# Video_critter_v01.net
KiCad netlist of a schematic drawn in EAGLE
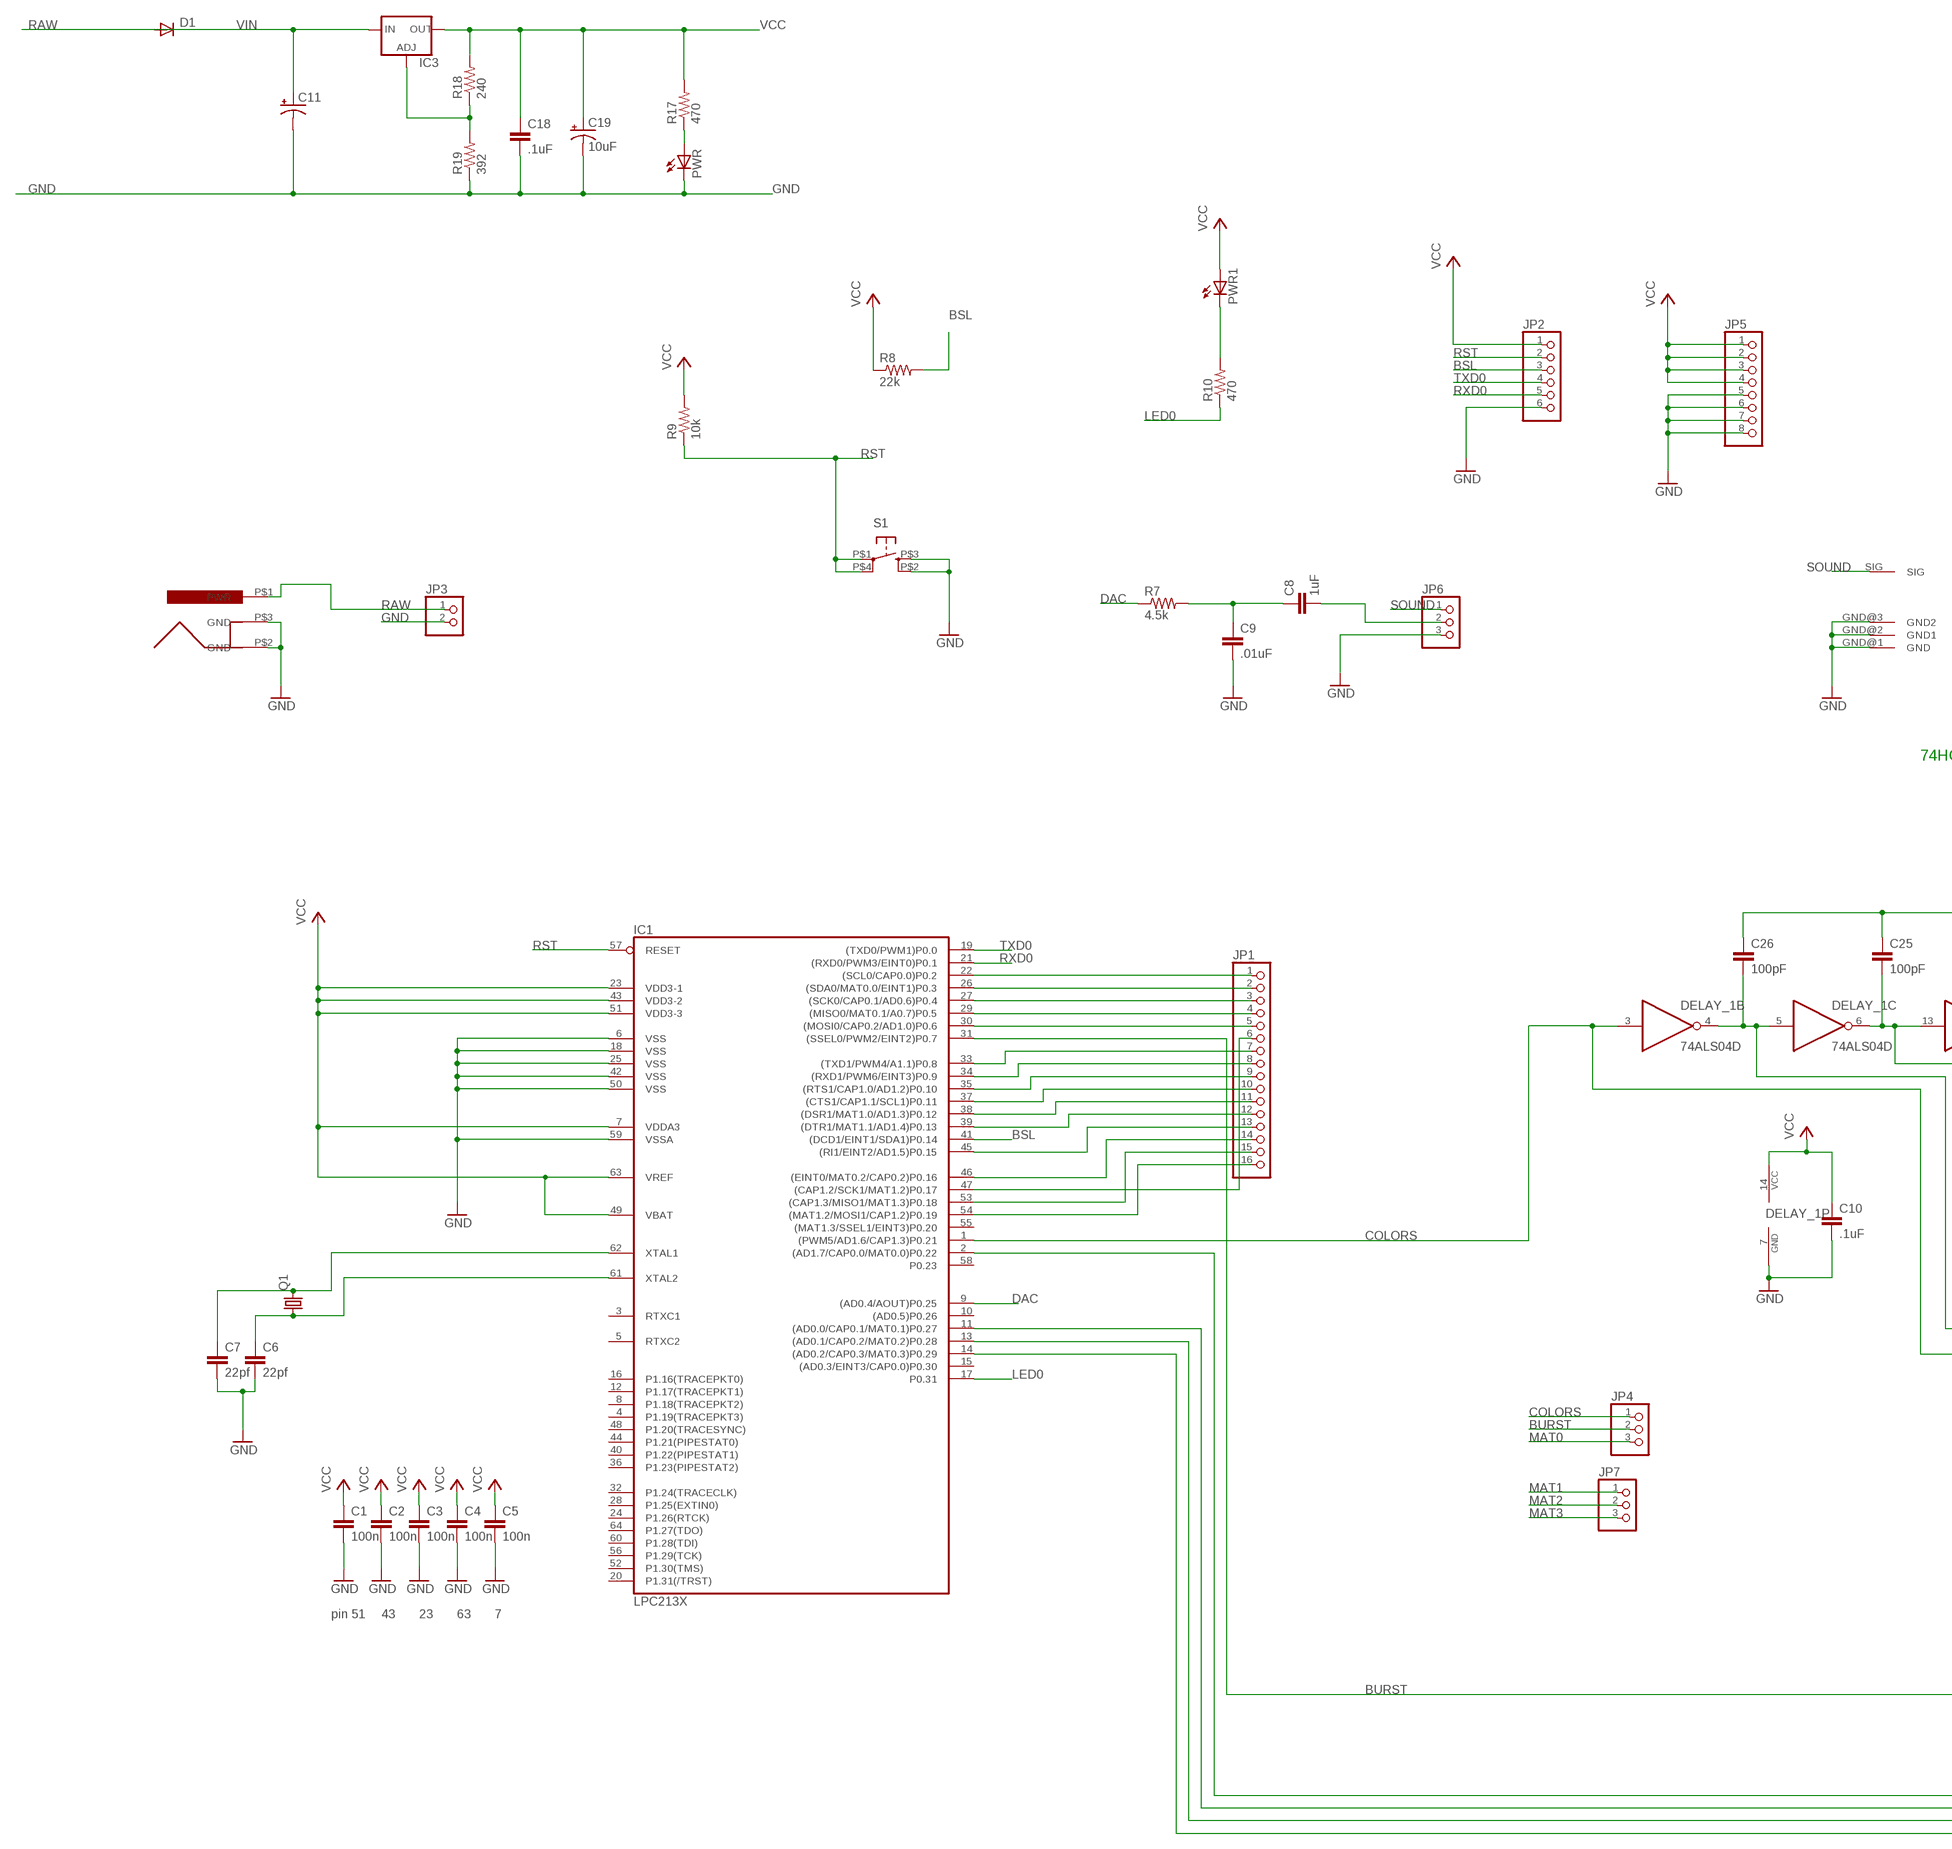
[diagram p0: schematic, sheet 1, part 1 of 2]
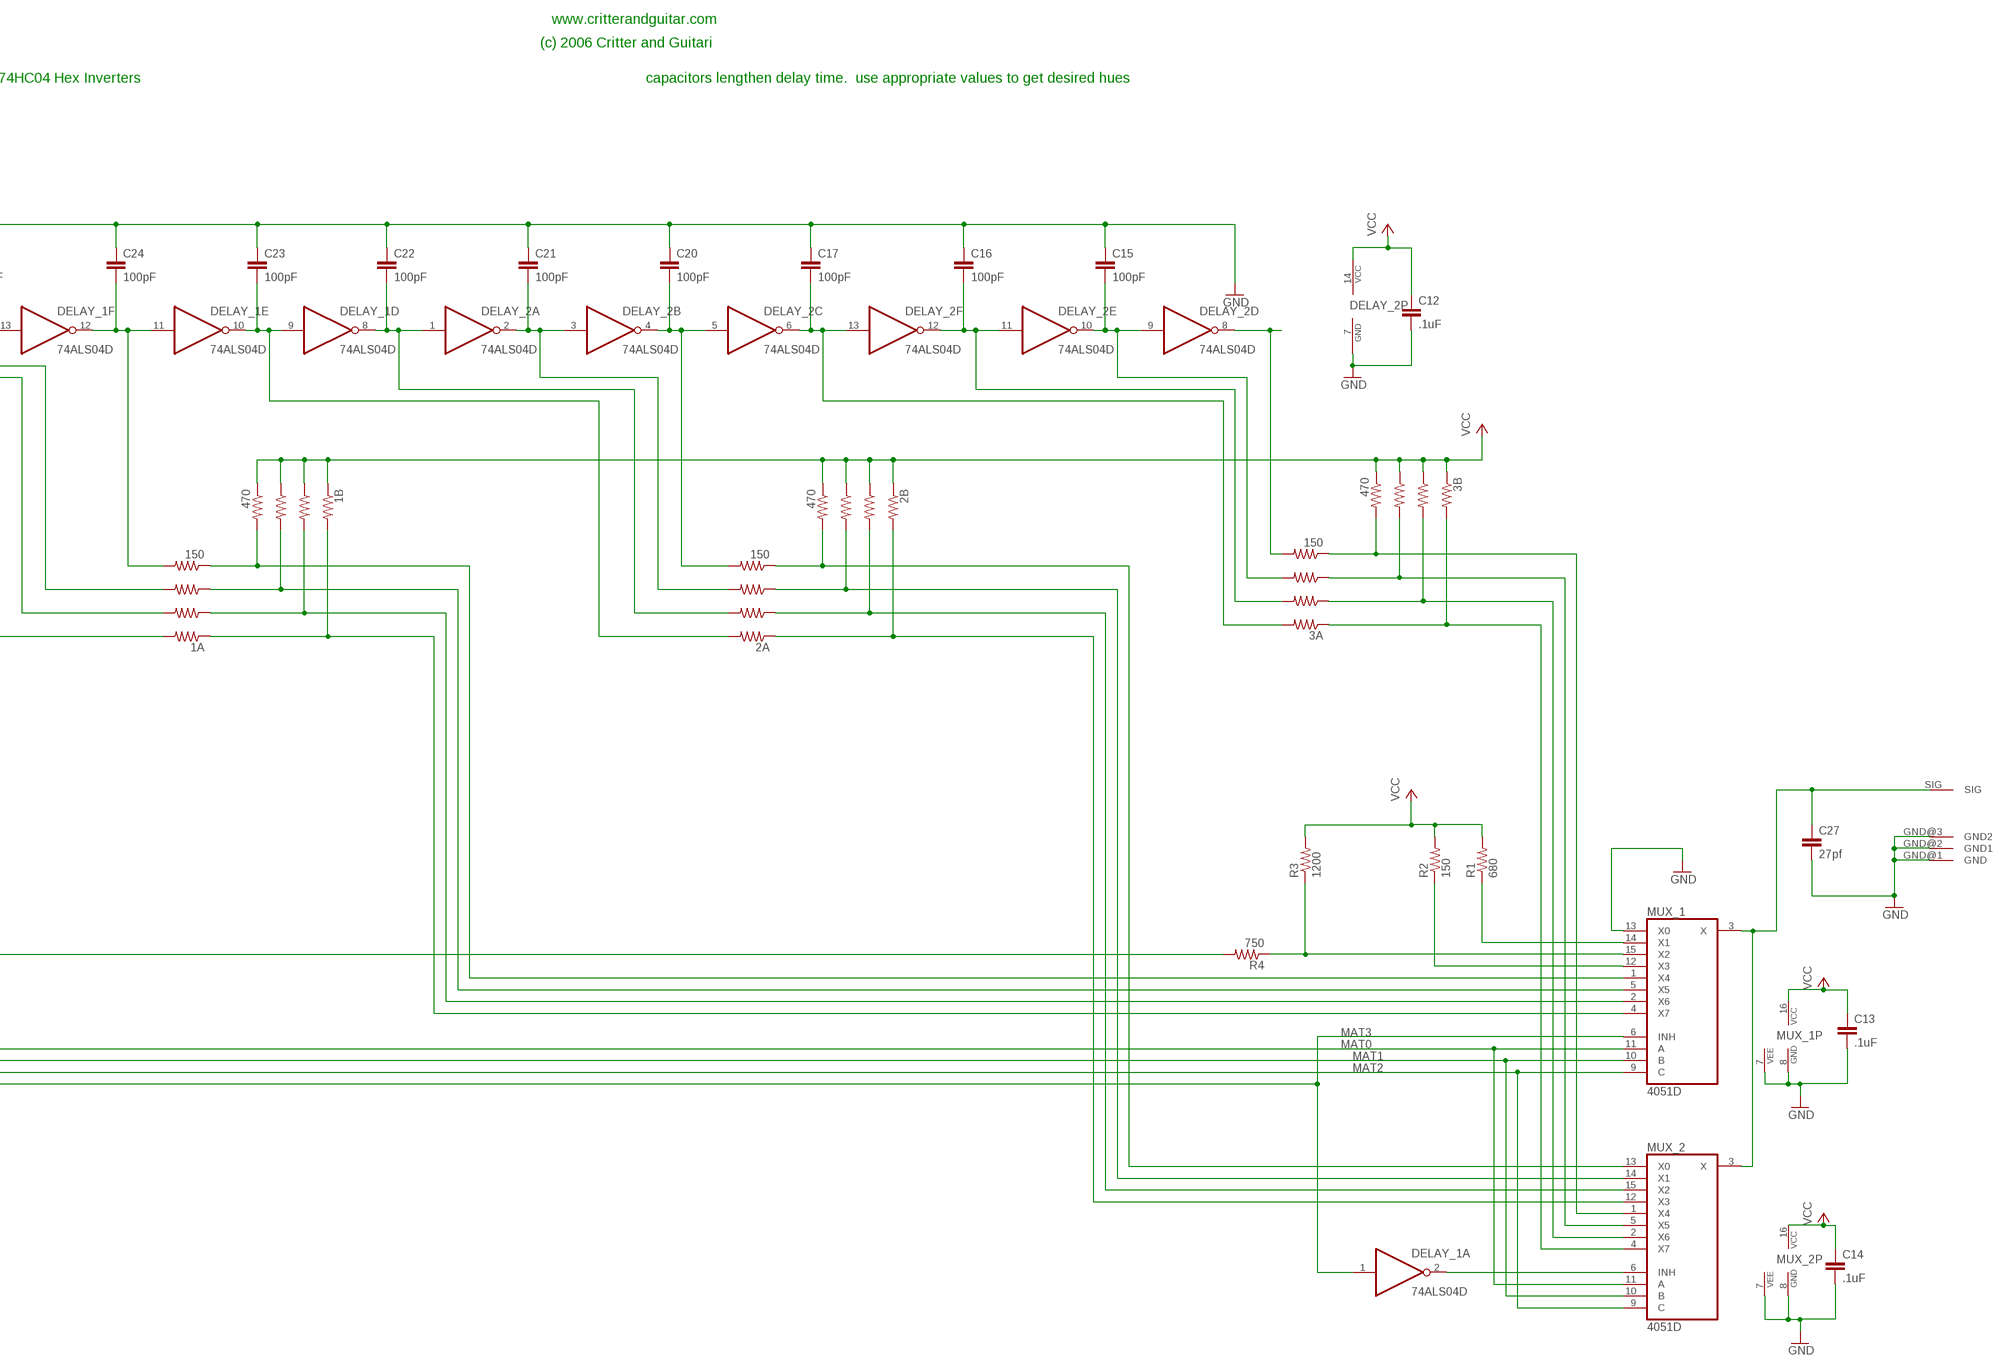
[diagram p1: schematic, sheet 1, part 2 of 2]

(export (version "E")
  (design (tool "Eeschema 10.0.6"))
  (components
    (comp (ref "1A")
      (value "150")
      (footprint "eagle-import:1206X4RESISTOR")
      (libsource (lib "eagle-import") (part "RESISTORX41206"))
    )
    (comp (ref "1B")
      (value "470")
      (footprint "eagle-import:1206X4RESISTOR")
      (libsource (lib "eagle-import") (part "RESISTORX41206"))
    )
    (comp (ref "2A")
      (value "150")
      (footprint "eagle-import:1206X4RESISTOR")
      (libsource (lib "eagle-import") (part "RESISTORX41206"))
    )
    (comp (ref "2B")
      (value "470")
      (footprint "eagle-import:1206X4RESISTOR")
      (libsource (lib "eagle-import") (part "RESISTORX41206"))
    )
    (comp (ref "3A")
      (value "150")
      (footprint "eagle-import:1206X4RESISTOR")
      (libsource (lib "eagle-import") (part "RESISTORX41206"))
    )
    (comp (ref "3B")
      (value "470")
      (footprint "eagle-import:1206X4RESISTOR")
      (libsource (lib "eagle-import") (part "RESISTORX41206"))
    )
    (comp (ref "C1")
      (value "100n")
      (footprint "eagle-import:C0603")
      (libsource (lib "eagle-import") (part "CAP0603"))
    )
    (comp (ref "C2")
      (value "100n")
      (footprint "eagle-import:C0603")
      (libsource (lib "eagle-import") (part "CAP0603"))
    )
    (comp (ref "C3")
      (value "100n")
      (footprint "eagle-import:C0603")
      (libsource (lib "eagle-import") (part "CAP0603"))
    )
    (comp (ref "C4")
      (value "100n")
      (footprint "eagle-import:C0603")
      (libsource (lib "eagle-import") (part "CAP0603"))
    )
    (comp (ref "C5")
      (value "100n")
      (footprint "eagle-import:C0603")
      (libsource (lib "eagle-import") (part "CAP0603"))
    )
    (comp (ref "C6")
      (value "22pf")
      (footprint "eagle-import:C0603")
      (libsource (lib "eagle-import") (part "CAP0603"))
    )
    (comp (ref "C7")
      (value "22pf")
      (footprint "eagle-import:C0603")
      (libsource (lib "eagle-import") (part "CAP0603"))
    )
    (comp (ref "C8")
      (value "1uF")
      (footprint "eagle-import:C0603")
      (libsource (lib "eagle-import") (part "CAP0603"))
    )
    (comp (ref "C9")
      (value ".01uF")
      (footprint "eagle-import:C0603")
      (libsource (lib "eagle-import") (part "CAP0603"))
    )
    (comp (ref "C10")
      (value ".1uF")
      (footprint "eagle-import:C0603")
      (libsource (lib "eagle-import") (part "CAP0603"))
    )
    (comp (ref "C11")
      (value "CPOL-USE3.5-8")
      (footprint "eagle-import:E3,5-8")
      (libsource (lib "eagle-import") (part "CPOL-USE3.5-8"))
    )
    (comp (ref "C12")
      (value ".1uF")
      (footprint "eagle-import:C0603")
      (libsource (lib "eagle-import") (part "CAP0603"))
    )
    (comp (ref "C13")
      (value ".1uF")
      (footprint "eagle-import:C0603")
      (libsource (lib "eagle-import") (part "CAP0603"))
    )
    (comp (ref "C14")
      (value ".1uF")
      (footprint "eagle-import:C0603")
      (libsource (lib "eagle-import") (part "CAP0603"))
    )
    (comp (ref "C15")
      (value "100pF")
      (footprint "eagle-import:C0603")
      (libsource (lib "eagle-import") (part "CAP0603"))
    )
    (comp (ref "C16")
      (value "100pF")
      (footprint "eagle-import:C0603")
      (libsource (lib "eagle-import") (part "CAP0603"))
    )
    (comp (ref "C17")
      (value "100pF")
      (footprint "eagle-import:C0603")
      (libsource (lib "eagle-import") (part "CAP0603"))
    )
    (comp (ref "C18")
      (value ".1uF")
      (footprint "eagle-import:C0603")
      (libsource (lib "eagle-import") (part "CAP0603"))
    )
    (comp (ref "C19")
      (value "10uF")
      (footprint "eagle-import:CPOL_1206")
      (libsource (lib "eagle-import") (part "CAP_POL1206"))
    )
    (comp (ref "C20")
      (value "100pF")
      (footprint "eagle-import:C0603")
      (libsource (lib "eagle-import") (part "CAP0603"))
    )
    (comp (ref "C21")
      (value "100pF")
      (footprint "eagle-import:C0603")
      (libsource (lib "eagle-import") (part "CAP0603"))
    )
    (comp (ref "C22")
      (value "100pF")
      (footprint "eagle-import:C0603")
      (libsource (lib "eagle-import") (part "CAP0603"))
    )
    (comp (ref "C23")
      (value "100pF")
      (footprint "eagle-import:C0603")
      (libsource (lib "eagle-import") (part "CAP0603"))
    )
    (comp (ref "C24")
      (value "100pF")
      (footprint "eagle-import:C0603")
      (libsource (lib "eagle-import") (part "CAP0603"))
    )
    (comp (ref "C25")
      (value "100pF")
      (footprint "eagle-import:C0603")
      (libsource (lib "eagle-import") (part "CAP0603"))
    )
    (comp (ref "C26")
      (value "100pF")
      (footprint "eagle-import:C0603")
      (libsource (lib "eagle-import") (part "CAP0603"))
    )
    (comp (ref "C27")
      (value "27pf")
      (footprint "eagle-import:C0603")
      (libsource (lib "eagle-import") (part "CAP0603"))
    )
    (comp (ref "D1")
      (value "DIODESMB")
      (footprint "eagle-import:SMB")
      (libsource (lib "eagle-import") (part "DIODESMB"))
    )
    (comp (ref "DELAY_1")
      (value "74ALS04D")
      (footprint "eagle-import:SO14")
      (libsource (lib "eagle-import") (part "7404DALS"))
    )
    (comp (ref "DELAY_2")
      (value "74ALS04D")
      (footprint "eagle-import:SO14")
      (libsource (lib "eagle-import") (part "7404DALS"))
    )
    (comp (ref "IC1")
      (value "LPC213X")
      (footprint "eagle-import:SQFP-S-10X10-64")
      (libsource (lib "eagle-import") (part "LPC213X"))
    )
    (comp (ref "IC3")
      (value "V_REG_FAN1117SOT223")
      (footprint "eagle-import:SOT223")
      (libsource (lib "eagle-import") (part "V_REG_FAN1117SOT223"))
    )
    (comp (ref "JP1")
      (value "PINHD-1X16")
      (footprint "eagle-import:1X16")
      (libsource (lib "eagle-import") (part "PINHD-1X16"))
    )
    (comp (ref "JP2")
      (value "PINHD-1X6")
      (footprint "eagle-import:1X06")
      (libsource (lib "eagle-import") (part "PINHD-1X6"))
    )
    (comp (ref "JP3")
      (value "PINHD-1X2")
      (footprint "eagle-import:1X02")
      (libsource (lib "eagle-import") (part "PINHD-1X2"))
    )
    (comp (ref "JP4")
      (value "PINHD-1X3")
      (footprint "eagle-import:1X03")
      (libsource (lib "eagle-import") (part "PINHD-1X3"))
    )
    (comp (ref "JP5")
      (value "PINHD-1X8")
      (footprint "eagle-import:1X08")
      (libsource (lib "eagle-import") (part "PINHD-1X8"))
    )
    (comp (ref "JP6")
      (value "PINHD-1X3")
      (footprint "eagle-import:1X03")
      (libsource (lib "eagle-import") (part "PINHD-1X3"))
    )
    (comp (ref "JP7")
      (value "PINHD-1X3")
      (footprint "eagle-import:1X03")
      (libsource (lib "eagle-import") (part "PINHD-1X3"))
    )
    (comp (ref "MUX_1")
      (value "4051D")
      (footprint "eagle-import:SO16")
      (libsource (lib "eagle-import") (part "4051D"))
    )
    (comp (ref "MUX_2")
      (value "4051D")
      (footprint "eagle-import:SO16")
      (libsource (lib "eagle-import") (part "4051D"))
    )
    (comp (ref "PWR")
      (value "LED1206")
      (footprint "eagle-import:CHIPLED_1206")
      (libsource (lib "eagle-import") (part "LED1206"))
    )
    (comp (ref "PWR1")
      (value "LED1206")
      (footprint "eagle-import:CHIPLED_1206")
      (libsource (lib "eagle-import") (part "LED1206"))
    )
    (comp (ref "Q1")
      (value "CRYSTALSOCKETED")
      (footprint "eagle-import:HC49U-SOCKETED")
      (libsource (lib "eagle-import") (part "CRYSTALSOCKETED"))
    )
    (comp (ref "R1")
      (value "680")
      (footprint "eagle-import:R0603")
      (libsource (lib "eagle-import") (part "RES0603"))
    )
    (comp (ref "R2")
      (value "150")
      (footprint "eagle-import:R0603")
      (libsource (lib "eagle-import") (part "RES0603"))
    )
    (comp (ref "R3")
      (value "1200")
      (footprint "eagle-import:R0603")
      (libsource (lib "eagle-import") (part "RES0603"))
    )
    (comp (ref "R4")
      (value "750")
      (footprint "eagle-import:R0603")
      (libsource (lib "eagle-import") (part "RES0603"))
    )
    (comp (ref "R7")
      (value "4.5k")
      (footprint "eagle-import:R0603")
      (libsource (lib "eagle-import") (part "RES0603"))
    )
    (comp (ref "R8")
      (value "22k")
      (footprint "eagle-import:R0603")
      (libsource (lib "eagle-import") (part "RES0603"))
    )
    (comp (ref "R9")
      (value "10k")
      (footprint "eagle-import:R0603")
      (libsource (lib "eagle-import") (part "RES0603"))
    )
    (comp (ref "R10")
      (value "470")
      (footprint "eagle-import:R0603")
      (libsource (lib "eagle-import") (part "RES0603"))
    )
    (comp (ref "R17")
      (value "470")
      (footprint "eagle-import:R0603")
      (libsource (lib "eagle-import") (part "RES0603"))
    )
    (comp (ref "R18")
      (value "240")
      (footprint "eagle-import:R0603")
      (libsource (lib "eagle-import") (part "RES0603"))
    )
    (comp (ref "R19")
      (value "392")
      (footprint "eagle-import:R0603")
      (libsource (lib "eagle-import") (part "RES0603"))
    )
    (comp (ref "S1")
      (value "TAC_SWITCH")
      (footprint "eagle-import:TACTILE_SWITCH_SMD")
      (libsource (lib "eagle-import") (part "TAC_SWITCH"))
    )
    (comp (ref "U$1")
      (value "POWER_JACK")
      (footprint "eagle-import:POWER_JACK")
      (libsource (lib "eagle-import") (part "POWER_JACKTHRU-HOLE"))
    )
    (comp (ref "U$5")
      (value "PHONO_PLUG")
      (footprint "eagle-import:PHONO_PCB")
      (libsource (lib "eagle-import") (part "PHONO_PLUG"))
    )
    (comp (ref "U$6")
      (value "PHONO_PLUG")
      (footprint "eagle-import:PHONO_PCB")
      (libsource (lib "eagle-import") (part "PHONO_PLUG"))
    )
  )
  (nets
    (net (code "1") (name "/BSL") (class "Default")
      (node (ref "IC1") (pin "41") (pinfunction "(DCD1/EINT1/SDA1)P0.14_41") (pintype "bidirectional"))
      (node (ref "JP2") (pin "3") (pinfunction "3_3") (pintype "passive"))
      (node (ref "R8") (pin "2") (pinfunction "2_2") (pintype "passive"))
    )
    (net (code "2") (name "/BURST") (class "Default")
      (node (ref "IC1") (pin "31") (pinfunction "(SSEL0/PWM2/EINT2)P0.7_31") (pintype "bidirectional"))
      (node (ref "JP4") (pin "2") (pinfunction "2_2") (pintype "passive"))
      (node (ref "R4") (pin "2") (pinfunction "2_2") (pintype "passive"))
    )
    (net (code "3") (name "/COLORS") (class "Default")
      (node (ref "1A") (pin "P$8") (pinfunction "7_P$8") (pintype "passive"))
      (node (ref "DELAY_1") (pin "3") (pinfunction "I_3") (pintype "input"))
      (node (ref "IC1") (pin "1") (pinfunction "(PWM5/AD1.6/CAP1.3)P0.21_1") (pintype "bidirectional"))
      (node (ref "JP4") (pin "1") (pinfunction "1_1") (pintype "passive"))
    )
    (net (code "4") (name "/DAC") (class "Default")
      (node (ref "IC1") (pin "9") (pinfunction "(AD0.4/AOUT)P0.25_9") (pintype "bidirectional"))
      (node (ref "R7") (pin "1") (pinfunction "1_1") (pintype "passive"))
    )
    (net (code "5") (name "/LED0") (class "Default")
      (node (ref "IC1") (pin "17") (pinfunction "P0.31_17") (pintype "output"))
      (node (ref "R10") (pin "1") (pinfunction "1_1") (pintype "passive"))
    )
    (net (code "6") (name "/MAT0") (class "Default")
      (node (ref "IC1") (pin "2") (pinfunction "(AD1.7/CAP0.0/MAT0.0)P0.22_2") (pintype "bidirectional"))
      (node (ref "JP4") (pin "3") (pinfunction "3_3") (pintype "passive"))
      (node (ref "MUX_1") (pin "11") (pinfunction "A_11") (pintype "input"))
      (node (ref "MUX_2") (pin "11") (pinfunction "A_11") (pintype "input"))
    )
    (net (code "7") (name "/MAT1") (class "Default")
      (node (ref "IC1") (pin "11") (pinfunction "(AD0.0/CAP0.1/MAT0.1)P0.27_11") (pintype "bidirectional"))
      (node (ref "JP7") (pin "1") (pinfunction "1_1") (pintype "passive"))
      (node (ref "MUX_1") (pin "10") (pinfunction "B_10") (pintype "input"))
      (node (ref "MUX_2") (pin "10") (pinfunction "B_10") (pintype "input"))
    )
    (net (code "8") (name "/MAT2") (class "Default")
      (node (ref "IC1") (pin "13") (pinfunction "(AD0.1/CAP0.2/MAT0.2)P0.28_13") (pintype "bidirectional"))
      (node (ref "JP7") (pin "2") (pinfunction "2_2") (pintype "passive"))
      (node (ref "MUX_1") (pin "9") (pinfunction "C_9") (pintype "input"))
      (node (ref "MUX_2") (pin "9") (pinfunction "C_9") (pintype "input"))
    )
    (net (code "9") (name "/MAT3") (class "Default")
      (node (ref "DELAY_1") (pin "1") (pinfunction "I_1") (pintype "input"))
      (node (ref "IC1") (pin "14") (pinfunction "(AD0.2/CAP0.3/MAT0.3)P0.29_14") (pintype "bidirectional"))
      (node (ref "JP7") (pin "3") (pinfunction "3_3") (pintype "passive"))
      (node (ref "MUX_1") (pin "6") (pinfunction "INH_6") (pintype "input"))
    )
    (net (code "10") (name "/RAW") (class "Default")
      (node (ref "D1") (pin "1") (pinfunction "C_1") (pintype "passive"))
      (node (ref "JP3") (pin "1") (pinfunction "1_1") (pintype "passive"))
      (node (ref "U$1") (pin "P$1") (pinfunction "PWR_P$1") (pintype "bidirectional"))
    )
    (net (code "11") (name "/RST") (class "Default")
      (node (ref "IC1") (pin "57") (pinfunction "RESET_57") (pintype "input"))
      (node (ref "JP2") (pin "2") (pinfunction "2_2") (pintype "passive"))
      (node (ref "R9") (pin "1") (pinfunction "1_1") (pintype "passive"))
      (node (ref "S1") (pin "P$1") (pinfunction "P_P$1") (pintype "passive"))
      (node (ref "S1") (pin "P$4") (pinfunction "P1_P$4") (pintype "passive"))
    )
    (net (code "12") (name "/RXD0") (class "Default")
      (node (ref "IC1") (pin "21") (pinfunction "(RXD0/PWM3/EINT0)P0.1_21") (pintype "bidirectional"))
      (node (ref "JP2") (pin "5") (pinfunction "5_5") (pintype "passive"))
    )
    (net (code "13") (name "/SOUND") (class "Default")
      (node (ref "JP6") (pin "1") (pinfunction "1_1") (pintype "passive"))
      (node (ref "U$5") (pin "SIG") (pinfunction "SIG_SIG") (pintype "bidirectional"))
    )
    (net (code "14") (name "/TXD0") (class "Default")
      (node (ref "IC1") (pin "19") (pinfunction "(TXD0/PWM1)P0.0_19") (pintype "bidirectional"))
      (node (ref "JP2") (pin "4") (pinfunction "4_4") (pintype "passive"))
    )
    (net (code "15") (name "/VIN") (class "Default")
      (node (ref "C11") (pin "+") (pinfunction "+_+") (pintype "passive"))
      (node (ref "D1") (pin "2") (pinfunction "A_2") (pintype "passive"))
      (node (ref "IC3") (pin "3") (pinfunction "IN_3") (pintype "input"))
    )
    (net (code "16") (name "GND") (class "Default")
      (node (ref "C1") (pin "2") (pinfunction "2_2") (pintype "passive"))
      (node (ref "C10") (pin "2") (pinfunction "2_2") (pintype "passive"))
      (node (ref "C11") (pin "-") (pinfunction "-_-") (pintype "passive"))
      (node (ref "C12") (pin "2") (pinfunction "2_2") (pintype "passive"))
      (node (ref "C13") (pin "2") (pinfunction "2_2") (pintype "passive"))
      (node (ref "C14") (pin "2") (pinfunction "2_2") (pintype "passive"))
      (node (ref "C15") (pin "1") (pinfunction "1_1") (pintype "passive"))
      (node (ref "C16") (pin "1") (pinfunction "1_1") (pintype "passive"))
      (node (ref "C17") (pin "1") (pinfunction "1_1") (pintype "passive"))
      (node (ref "C18") (pin "2") (pinfunction "2_2") (pintype "passive"))
      (node (ref "C19") (pin "C") (pinfunction "-_C") (pintype "passive"))
      (node (ref "C2") (pin "2") (pinfunction "2_2") (pintype "passive"))
      (node (ref "C20") (pin "1") (pinfunction "1_1") (pintype "passive"))
      (node (ref "C21") (pin "1") (pinfunction "1_1") (pintype "passive"))
      (node (ref "C22") (pin "1") (pinfunction "1_1") (pintype "passive"))
      (node (ref "C23") (pin "1") (pinfunction "1_1") (pintype "passive"))
      (node (ref "C24") (pin "1") (pinfunction "1_1") (pintype "passive"))
      (node (ref "C25") (pin "1") (pinfunction "1_1") (pintype "passive"))
      (node (ref "C26") (pin "1") (pinfunction "1_1") (pintype "passive"))
      (node (ref "C27") (pin "2") (pinfunction "2_2") (pintype "passive"))
      (node (ref "C3") (pin "2") (pinfunction "2_2") (pintype "passive"))
      (node (ref "C4") (pin "2") (pinfunction "2_2") (pintype "passive"))
      (node (ref "C5") (pin "2") (pinfunction "2_2") (pintype "passive"))
      (node (ref "C6") (pin "2") (pinfunction "2_2") (pintype "passive"))
      (node (ref "C7") (pin "2") (pinfunction "2_2") (pintype "passive"))
      (node (ref "C9") (pin "2") (pinfunction "2_2") (pintype "passive"))
      (node (ref "DELAY_1") (pin "7") (pinfunction "GND_7") (pintype "power_in"))
      (node (ref "DELAY_2") (pin "7") (pinfunction "GND_7") (pintype "power_in"))
      (node (ref "IC1") (pin "18") (pinfunction "VSS_18") (pintype "power_in"))
      (node (ref "IC1") (pin "25") (pinfunction "VSS_25") (pintype "power_in"))
      (node (ref "IC1") (pin "42") (pinfunction "VSS_42") (pintype "power_in"))
      (node (ref "IC1") (pin "50") (pinfunction "VSS_50") (pintype "power_in"))
      (node (ref "IC1") (pin "59") (pinfunction "VSSA_59") (pintype "power_in"))
      (node (ref "IC1") (pin "6") (pinfunction "VSS_6") (pintype "power_in"))
      (node (ref "JP2") (pin "6") (pinfunction "6_6") (pintype "passive"))
      (node (ref "JP3") (pin "2") (pinfunction "2_2") (pintype "passive"))
      (node (ref "JP5") (pin "5") (pinfunction "5_5") (pintype "passive"))
      (node (ref "JP5") (pin "6") (pinfunction "6_6") (pintype "passive"))
      (node (ref "JP5") (pin "7") (pinfunction "7_7") (pintype "passive"))
      (node (ref "JP5") (pin "8") (pinfunction "8_8") (pintype "passive"))
      (node (ref "JP6") (pin "3") (pinfunction "3_3") (pintype "passive"))
      (node (ref "MUX_1") (pin "13") (pinfunction "X0_13") (pintype "bidirectional"))
      (node (ref "MUX_1") (pin "7") (pinfunction "VEE_7") (pintype "power_in"))
      (node (ref "MUX_1") (pin "8") (pinfunction "GND_8") (pintype "power_in"))
      (node (ref "MUX_2") (pin "7") (pinfunction "VEE_7") (pintype "power_in"))
      (node (ref "MUX_2") (pin "8") (pinfunction "GND_8") (pintype "power_in"))
      (node (ref "PWR") (pin "C") (pinfunction "C_C") (pintype "passive"))
      (node (ref "R19") (pin "1") (pinfunction "1_1") (pintype "passive"))
      (node (ref "S1") (pin "P$2") (pinfunction "S1_P$2") (pintype "passive"))
      (node (ref "S1") (pin "P$3") (pinfunction "S_P$3") (pintype "passive"))
      (node (ref "U$1") (pin "P$2") (pinfunction "GND_P$2") (pintype "bidirectional"))
      (node (ref "U$1") (pin "P$3") (pinfunction "GND_P$3") (pintype "bidirectional"))
      (node (ref "U$5") (pin "GND@1") (pinfunction "GND_GND@1") (pintype "bidirectional"))
      (node (ref "U$5") (pin "GND@2") (pinfunction "GND1_GND@2") (pintype "bidirectional"))
      (node (ref "U$5") (pin "GND@3") (pinfunction "GND2_GND@3") (pintype "bidirectional"))
      (node (ref "U$6") (pin "GND@1") (pinfunction "GND_GND@1") (pintype "bidirectional"))
      (node (ref "U$6") (pin "GND@2") (pinfunction "GND1_GND@2") (pintype "bidirectional"))
      (node (ref "U$6") (pin "GND@3") (pinfunction "GND2_GND@3") (pintype "bidirectional"))
    )
    (net (code "17") (name "Net-(1A-1)") (class "Default")
      (node (ref "1A") (pin "P$3") (pinfunction "1_P$3") (pintype "passive"))
      (node (ref "1B") (pin "P$4") (pinfunction "2_P$4") (pintype "passive"))
      (node (ref "MUX_1") (pin "5") (pinfunction "X5_5") (pintype "bidirectional"))
    )
    (net (code "18") (name "Net-(1A-2)") (class "Default")
      (node (ref "1A") (pin "P$4") (pinfunction "2_P$4") (pintype "passive"))
      (node (ref "C25") (pin "2") (pinfunction "2_2") (pintype "passive"))
      (node (ref "DELAY_1") (pin "13") (pinfunction "I_13") (pintype "input"))
      (node (ref "DELAY_1") (pin "6") (pinfunction "O_6") (pintype "output"))
    )
    (net (code "19") (name "Net-(1A-3)") (class "Default")
      (node (ref "1A") (pin "P$6") (pinfunction "3_P$6") (pintype "passive"))
      (node (ref "C26") (pin "2") (pinfunction "2_2") (pintype "passive"))
      (node (ref "DELAY_1") (pin "4") (pinfunction "O_4") (pintype "output"))
      (node (ref "DELAY_1") (pin "5") (pinfunction "I_5") (pintype "input"))
    )
    (net (code "20") (name "Net-(1A-4)") (class "Default")
      (node (ref "1A") (pin "P$5") (pinfunction "4_P$5") (pintype "passive"))
      (node (ref "1B") (pin "P$6") (pinfunction "3_P$6") (pintype "passive"))
      (node (ref "MUX_1") (pin "2") (pinfunction "X6_2") (pintype "bidirectional"))
    )
    (net (code "21") (name "Net-(1A-5)") (class "Default")
      (node (ref "1A") (pin "P$2") (pinfunction "5_P$2") (pintype "passive"))
      (node (ref "C24") (pin "2") (pinfunction "2_2") (pintype "passive"))
      (node (ref "DELAY_1") (pin "11") (pinfunction "I_11") (pintype "input"))
      (node (ref "DELAY_1") (pin "12") (pinfunction "O_12") (pintype "output"))
    )
    (net (code "22") (name "Net-(1A-6)") (class "Default")
      (node (ref "1A") (pin "P$1") (pinfunction "6_P$1") (pintype "passive"))
      (node (ref "1B") (pin "P$2") (pinfunction "5_P$2") (pintype "passive"))
      (node (ref "MUX_1") (pin "1") (pinfunction "X4_1") (pintype "bidirectional"))
    )
    (net (code "23") (name "Net-(1A-8)") (class "Default")
      (node (ref "1A") (pin "P$7") (pinfunction "8_P$7") (pintype "passive"))
      (node (ref "1B") (pin "P$8") (pinfunction "7_P$8") (pintype "passive"))
      (node (ref "MUX_1") (pin "4") (pinfunction "X7_4") (pintype "bidirectional"))
    )
    (net (code "24") (name "Net-(2A-1)") (class "Default")
      (node (ref "2A") (pin "P$3") (pinfunction "1_P$3") (pintype "passive"))
      (node (ref "2B") (pin "P$4") (pinfunction "2_P$4") (pintype "passive"))
      (node (ref "MUX_2") (pin "14") (pinfunction "X1_14") (pintype "bidirectional"))
    )
    (net (code "25") (name "Net-(2A-2)") (class "Default")
      (node (ref "2A") (pin "P$4") (pinfunction "2_P$4") (pintype "passive"))
      (node (ref "C21") (pin "2") (pinfunction "2_2") (pintype "passive"))
      (node (ref "DELAY_2") (pin "2") (pinfunction "O_2") (pintype "output"))
      (node (ref "DELAY_2") (pin "3") (pinfunction "I_3") (pintype "input"))
    )
    (net (code "26") (name "Net-(2A-3)") (class "Default")
      (node (ref "2A") (pin "P$6") (pinfunction "3_P$6") (pintype "passive"))
      (node (ref "C22") (pin "2") (pinfunction "2_2") (pintype "passive"))
      (node (ref "DELAY_1") (pin "8") (pinfunction "O_8") (pintype "output"))
      (node (ref "DELAY_2") (pin "1") (pinfunction "I_1") (pintype "input"))
    )
    (net (code "27") (name "Net-(2A-4)") (class "Default")
      (node (ref "2A") (pin "P$5") (pinfunction "4_P$5") (pintype "passive"))
      (node (ref "2B") (pin "P$6") (pinfunction "3_P$6") (pintype "passive"))
      (node (ref "MUX_2") (pin "15") (pinfunction "X2_15") (pintype "bidirectional"))
    )
    (net (code "28") (name "Net-(2A-5)") (class "Default")
      (node (ref "2A") (pin "P$2") (pinfunction "5_P$2") (pintype "passive"))
      (node (ref "C20") (pin "2") (pinfunction "2_2") (pintype "passive"))
      (node (ref "DELAY_2") (pin "4") (pinfunction "O_4") (pintype "output"))
      (node (ref "DELAY_2") (pin "5") (pinfunction "I_5") (pintype "input"))
    )
    (net (code "29") (name "Net-(2A-6)") (class "Default")
      (node (ref "2A") (pin "P$1") (pinfunction "6_P$1") (pintype "passive"))
      (node (ref "2B") (pin "P$2") (pinfunction "5_P$2") (pintype "passive"))
      (node (ref "MUX_2") (pin "13") (pinfunction "X0_13") (pintype "bidirectional"))
    )
    (net (code "30") (name "Net-(2A-7)") (class "Default")
      (node (ref "2A") (pin "P$8") (pinfunction "7_P$8") (pintype "passive"))
      (node (ref "C23") (pin "2") (pinfunction "2_2") (pintype "passive"))
      (node (ref "DELAY_1") (pin "10") (pinfunction "O_10") (pintype "output"))
      (node (ref "DELAY_1") (pin "9") (pinfunction "I_9") (pintype "input"))
    )
    (net (code "31") (name "Net-(2A-8)") (class "Default")
      (node (ref "2A") (pin "P$7") (pinfunction "8_P$7") (pintype "passive"))
      (node (ref "2B") (pin "P$8") (pinfunction "7_P$8") (pintype "passive"))
      (node (ref "MUX_2") (pin "12") (pinfunction "X3_12") (pintype "bidirectional"))
    )
    (net (code "32") (name "Net-(3A-1)") (class "Default")
      (node (ref "3A") (pin "P$3") (pinfunction "1_P$3") (pintype "passive"))
      (node (ref "3B") (pin "P$4") (pinfunction "2_P$4") (pintype "passive"))
      (node (ref "MUX_2") (pin "5") (pinfunction "X5_5") (pintype "bidirectional"))
    )
    (net (code "33") (name "Net-(3A-2)") (class "Default")
      (node (ref "3A") (pin "P$4") (pinfunction "2_P$4") (pintype "passive"))
      (node (ref "C15") (pin "2") (pinfunction "2_2") (pintype "passive"))
      (node (ref "DELAY_2") (pin "10") (pinfunction "O_10") (pintype "output"))
      (node (ref "DELAY_2") (pin "9") (pinfunction "I_9") (pintype "input"))
    )
    (net (code "34") (name "Net-(3A-3)") (class "Default")
      (node (ref "3A") (pin "P$6") (pinfunction "3_P$6") (pintype "passive"))
      (node (ref "C16") (pin "2") (pinfunction "2_2") (pintype "passive"))
      (node (ref "DELAY_2") (pin "11") (pinfunction "I_11") (pintype "input"))
      (node (ref "DELAY_2") (pin "12") (pinfunction "O_12") (pintype "output"))
    )
    (net (code "35") (name "Net-(3A-4)") (class "Default")
      (node (ref "3A") (pin "P$5") (pinfunction "4_P$5") (pintype "passive"))
      (node (ref "3B") (pin "P$6") (pinfunction "3_P$6") (pintype "passive"))
      (node (ref "MUX_2") (pin "2") (pinfunction "X6_2") (pintype "bidirectional"))
    )
    (net (code "36") (name "Net-(3A-5)") (class "Default")
      (node (ref "3A") (pin "P$2") (pinfunction "5_P$2") (pintype "passive"))
      (node (ref "DELAY_2") (pin "8") (pinfunction "O_8") (pintype "output"))
    )
    (net (code "37") (name "Net-(3A-6)") (class "Default")
      (node (ref "3A") (pin "P$1") (pinfunction "6_P$1") (pintype "passive"))
      (node (ref "3B") (pin "P$2") (pinfunction "5_P$2") (pintype "passive"))
      (node (ref "MUX_2") (pin "1") (pinfunction "X4_1") (pintype "bidirectional"))
    )
    (net (code "38") (name "Net-(3A-7)") (class "Default")
      (node (ref "3A") (pin "P$8") (pinfunction "7_P$8") (pintype "passive"))
      (node (ref "C17") (pin "2") (pinfunction "2_2") (pintype "passive"))
      (node (ref "DELAY_2") (pin "13") (pinfunction "I_13") (pintype "input"))
      (node (ref "DELAY_2") (pin "6") (pinfunction "O_6") (pintype "output"))
    )
    (net (code "39") (name "Net-(3A-8)") (class "Default")
      (node (ref "3A") (pin "P$7") (pinfunction "8_P$7") (pintype "passive"))
      (node (ref "3B") (pin "P$8") (pinfunction "7_P$8") (pintype "passive"))
      (node (ref "MUX_2") (pin "4") (pinfunction "X7_4") (pintype "bidirectional"))
    )
    (net (code "40") (name "Net-(C8-Pad1)") (class "Default")
      (node (ref "C8") (pin "1") (pinfunction "1_1") (pintype "passive"))
      (node (ref "C9") (pin "1") (pinfunction "1_1") (pintype "passive"))
      (node (ref "R7") (pin "2") (pinfunction "2_2") (pintype "passive"))
    )
    (net (code "41") (name "Net-(C8-Pad2)") (class "Default")
      (node (ref "C8") (pin "2") (pinfunction "2_2") (pintype "passive"))
      (node (ref "JP6") (pin "2") (pinfunction "2_2") (pintype "passive"))
    )
    (net (code "42") (name "Net-(DELAY_1A-O)") (class "Default")
      (node (ref "DELAY_1") (pin "2") (pinfunction "O_2") (pintype "output"))
      (node (ref "MUX_2") (pin "6") (pinfunction "INH_6") (pintype "input"))
    )
    (net (code "43") (name "Net-(IC1-(CAP1.2{slash}SCK1{slash}MAT1.2)P0.17)") (class "Default")
      (node (ref "IC1") (pin "47") (pinfunction "(CAP1.2/SCK1/MAT1.2)P0.17_47") (pintype "bidirectional"))
      (node (ref "JP1") (pin "6") (pinfunction "6_6") (pintype "passive"))
    )
    (net (code "44") (name "Net-(IC1-(CAP1.3{slash}MISO1{slash}MAT1.3)P0.18)") (class "Default")
      (node (ref "IC1") (pin "53") (pinfunction "(CAP1.3/MISO1/MAT1.3)P0.18_53") (pintype "bidirectional"))
      (node (ref "JP1") (pin "15") (pinfunction "15_15") (pintype "passive"))
    )
    (net (code "45") (name "Net-(IC1-(CTS1{slash}CAP1.1{slash}SCL1)P0.11)") (class "Default")
      (node (ref "IC1") (pin "37") (pinfunction "(CTS1/CAP1.1/SCL1)P0.11_37") (pintype "bidirectional"))
      (node (ref "JP1") (pin "10") (pinfunction "10_10") (pintype "passive"))
    )
    (net (code "46") (name "Net-(IC1-(DSR1{slash}MAT1.0{slash}AD1.3)P0.12)") (class "Default")
      (node (ref "IC1") (pin "38") (pinfunction "(DSR1/MAT1.0/AD1.3)P0.12_38") (pintype "bidirectional"))
      (node (ref "JP1") (pin "11") (pinfunction "11_11") (pintype "passive"))
    )
    (net (code "47") (name "Net-(IC1-(DTR1{slash}MAT1.1{slash}AD1.4)P0.13)") (class "Default")
      (node (ref "IC1") (pin "39") (pinfunction "(DTR1/MAT1.1/AD1.4)P0.13_39") (pintype "bidirectional"))
      (node (ref "JP1") (pin "12") (pinfunction "12_12") (pintype "passive"))
    )
    (net (code "48") (name "Net-(IC1-(EINT0{slash}MAT0.2{slash}CAP0.2)P0.16)") (class "Default")
      (node (ref "IC1") (pin "46") (pinfunction "(EINT0/MAT0.2/CAP0.2)P0.16_46") (pintype "bidirectional"))
      (node (ref "JP1") (pin "14") (pinfunction "14_14") (pintype "passive"))
    )
    (net (code "49") (name "Net-(IC1-(MAT1.2{slash}MOSI1{slash}CAP1.2)P0.19)") (class "Default")
      (node (ref "IC1") (pin "54") (pinfunction "(MAT1.2/MOSI1/CAP1.2)P0.19_54") (pintype "bidirectional"))
      (node (ref "JP1") (pin "16") (pinfunction "16_16") (pintype "passive"))
    )
    (net (code "50") (name "Net-(IC1-(MISO0{slash}MAT0.1{slash}A0.7)P0.5)") (class "Default")
      (node (ref "IC1") (pin "29") (pinfunction "(MISO0/MAT0.1/A0.7)P0.5_29") (pintype "bidirectional"))
      (node (ref "JP1") (pin "4") (pinfunction "4_4") (pintype "passive"))
    )
    (net (code "51") (name "Net-(IC1-(MOSI0{slash}CAP0.2{slash}AD1.0)P0.6)") (class "Default")
      (node (ref "IC1") (pin "30") (pinfunction "(MOSI0/CAP0.2/AD1.0)P0.6_30") (pintype "bidirectional"))
      (node (ref "JP1") (pin "5") (pinfunction "5_5") (pintype "passive"))
    )
    (net (code "52") (name "Net-(IC1-(RI1{slash}EINT2{slash}AD1.5)P0.15)") (class "Default")
      (node (ref "IC1") (pin "45") (pinfunction "(RI1/EINT2/AD1.5)P0.15_45") (pintype "bidirectional"))
      (node (ref "JP1") (pin "13") (pinfunction "13_13") (pintype "passive"))
    )
    (net (code "53") (name "Net-(IC1-(RTS1{slash}CAP1.0{slash}AD1.2)P0.10)") (class "Default")
      (node (ref "IC1") (pin "35") (pinfunction "(RTS1/CAP1.0/AD1.2)P0.10_35") (pintype "bidirectional"))
      (node (ref "JP1") (pin "9") (pinfunction "9_9") (pintype "passive"))
    )
    (net (code "54") (name "Net-(IC1-(RXD1{slash}PWM6{slash}EINT3)P0.9)") (class "Default")
      (node (ref "IC1") (pin "34") (pinfunction "(RXD1/PWM6/EINT3)P0.9_34") (pintype "bidirectional"))
      (node (ref "JP1") (pin "8") (pinfunction "8_8") (pintype "passive"))
    )
    (net (code "55") (name "Net-(IC1-(SCK0{slash}CAP0.1{slash}AD0.6)P0.4)") (class "Default")
      (node (ref "IC1") (pin "27") (pinfunction "(SCK0/CAP0.1/AD0.6)P0.4_27") (pintype "bidirectional"))
      (node (ref "JP1") (pin "3") (pinfunction "3_3") (pintype "passive"))
    )
    (net (code "56") (name "Net-(IC1-(SCL0{slash}CAP0.0)P0.2)") (class "Default")
      (node (ref "IC1") (pin "22") (pinfunction "(SCL0/CAP0.0)P0.2_22") (pintype "bidirectional"))
      (node (ref "JP1") (pin "1") (pinfunction "1_1") (pintype "passive"))
    )
    (net (code "57") (name "Net-(IC1-(SDA0{slash}MAT0.0{slash}EINT1)P0.3)") (class "Default")
      (node (ref "IC1") (pin "26") (pinfunction "(SDA0/MAT0.0/EINT1)P0.3_26") (pintype "bidirectional"))
      (node (ref "JP1") (pin "2") (pinfunction "2_2") (pintype "passive"))
    )
    (net (code "58") (name "Net-(IC1-(TXD1{slash}PWM4{slash}A1.1)P0.8)") (class "Default")
      (node (ref "IC1") (pin "33") (pinfunction "(TXD1/PWM4/A1.1)P0.8_33") (pintype "bidirectional"))
      (node (ref "JP1") (pin "7") (pinfunction "7_7") (pintype "passive"))
    )
    (net (code "59") (name "Net-(IC1-XTAL1)") (class "Default")
      (node (ref "C7") (pin "1") (pinfunction "1_1") (pintype "passive"))
      (node (ref "IC1") (pin "62") (pinfunction "XTAL1_62") (pintype "input"))
      (node (ref "Q1") (pin "2") (pinfunction "2_2") (pintype "passive"))
    )
    (net (code "60") (name "Net-(IC1-XTAL2)") (class "Default")
      (node (ref "C6") (pin "1") (pinfunction "1_1") (pintype "passive"))
      (node (ref "IC1") (pin "61") (pinfunction "XTAL2_61") (pintype "output"))
      (node (ref "Q1") (pin "1") (pinfunction "1_1") (pintype "passive"))
    )
    (net (code "61") (name "Net-(IC3-ADJ)") (class "Default")
      (node (ref "IC3") (pin "1") (pinfunction "ADJ_1") (pintype "input"))
      (node (ref "R18") (pin "1") (pinfunction "1_1") (pintype "passive"))
      (node (ref "R19") (pin "2") (pinfunction "2_2") (pintype "passive"))
    )
    (net (code "62") (name "Net-(MUX_1A-X)") (class "Default")
      (node (ref "C27") (pin "1") (pinfunction "1_1") (pintype "passive"))
      (node (ref "MUX_1") (pin "3") (pinfunction "X_3") (pintype "bidirectional"))
      (node (ref "MUX_2") (pin "3") (pinfunction "X_3") (pintype "bidirectional"))
      (node (ref "U$6") (pin "SIG") (pinfunction "SIG_SIG") (pintype "bidirectional"))
    )
    (net (code "63") (name "Net-(MUX_1A-X1)") (class "Default")
      (node (ref "MUX_1") (pin "14") (pinfunction "X1_14") (pintype "bidirectional"))
      (node (ref "R1") (pin "1") (pinfunction "1_1") (pintype "passive"))
    )
    (net (code "64") (name "Net-(MUX_1A-X2)") (class "Default")
      (node (ref "MUX_1") (pin "15") (pinfunction "X2_15") (pintype "bidirectional"))
      (node (ref "R3") (pin "1") (pinfunction "1_1") (pintype "passive"))
      (node (ref "R4") (pin "1") (pinfunction "1_1") (pintype "passive"))
    )
    (net (code "65") (name "Net-(MUX_1A-X3)") (class "Default")
      (node (ref "MUX_1") (pin "12") (pinfunction "X3_12") (pintype "bidirectional"))
      (node (ref "R2") (pin "1") (pinfunction "1_1") (pintype "passive"))
    )
    (net (code "66") (name "Net-(PWR-PadA)") (class "Default")
      (node (ref "PWR") (pin "A") (pinfunction "A_A") (pintype "passive"))
      (node (ref "R17") (pin "1") (pinfunction "1_1") (pintype "passive"))
    )
    (net (code "67") (name "Net-(PWR1-PadC)") (class "Default")
      (node (ref "PWR1") (pin "C") (pinfunction "C_C") (pintype "passive"))
      (node (ref "R10") (pin "2") (pinfunction "2_2") (pintype "passive"))
    )
    (net (code "68") (name "VCC") (class "Default")
      (node (ref "1B") (pin "P$1") (pinfunction "6_P$1") (pintype "passive"))
      (node (ref "1B") (pin "P$3") (pinfunction "1_P$3") (pintype "passive"))
      (node (ref "1B") (pin "P$5") (pinfunction "4_P$5") (pintype "passive"))
      (node (ref "1B") (pin "P$7") (pinfunction "8_P$7") (pintype "passive"))
      (node (ref "2B") (pin "P$1") (pinfunction "6_P$1") (pintype "passive"))
      (node (ref "2B") (pin "P$3") (pinfunction "1_P$3") (pintype "passive"))
      (node (ref "2B") (pin "P$5") (pinfunction "4_P$5") (pintype "passive"))
      (node (ref "2B") (pin "P$7") (pinfunction "8_P$7") (pintype "passive"))
      (node (ref "3B") (pin "P$1") (pinfunction "6_P$1") (pintype "passive"))
      (node (ref "3B") (pin "P$3") (pinfunction "1_P$3") (pintype "passive"))
      (node (ref "3B") (pin "P$5") (pinfunction "4_P$5") (pintype "passive"))
      (node (ref "3B") (pin "P$7") (pinfunction "8_P$7") (pintype "passive"))
      (node (ref "C1") (pin "1") (pinfunction "1_1") (pintype "passive"))
      (node (ref "C10") (pin "1") (pinfunction "1_1") (pintype "passive"))
      (node (ref "C12") (pin "1") (pinfunction "1_1") (pintype "passive"))
      (node (ref "C13") (pin "1") (pinfunction "1_1") (pintype "passive"))
      (node (ref "C14") (pin "1") (pinfunction "1_1") (pintype "passive"))
      (node (ref "C18") (pin "1") (pinfunction "1_1") (pintype "passive"))
      (node (ref "C19") (pin "A") (pinfunction "+_A") (pintype "passive"))
      (node (ref "C2") (pin "1") (pinfunction "1_1") (pintype "passive"))
      (node (ref "C3") (pin "1") (pinfunction "1_1") (pintype "passive"))
      (node (ref "C4") (pin "1") (pinfunction "1_1") (pintype "passive"))
      (node (ref "C5") (pin "1") (pinfunction "1_1") (pintype "passive"))
      (node (ref "DELAY_1") (pin "14") (pinfunction "VCC_14") (pintype "power_in"))
      (node (ref "DELAY_2") (pin "14") (pinfunction "VCC_14") (pintype "power_in"))
      (node (ref "IC1") (pin "23") (pinfunction "VDD3-1_23") (pintype "power_in"))
      (node (ref "IC1") (pin "43") (pinfunction "VDD3-2_43") (pintype "power_in"))
      (node (ref "IC1") (pin "49") (pinfunction "VBAT_49") (pintype "power_in"))
      (node (ref "IC1") (pin "51") (pinfunction "VDD3-3_51") (pintype "power_in"))
      (node (ref "IC1") (pin "63") (pinfunction "VREF_63") (pintype "input"))
      (node (ref "IC1") (pin "7") (pinfunction "VDDA3_7") (pintype "power_in"))
      (node (ref "IC3") (pin "2") (pinfunction "OUT_2") (pintype "passive"))
      (node (ref "JP2") (pin "1") (pinfunction "1_1") (pintype "passive"))
      (node (ref "JP5") (pin "1") (pinfunction "1_1") (pintype "passive"))
      (node (ref "JP5") (pin "2") (pinfunction "2_2") (pintype "passive"))
      (node (ref "JP5") (pin "3") (pinfunction "3_3") (pintype "passive"))
      (node (ref "JP5") (pin "4") (pinfunction "4_4") (pintype "passive"))
      (node (ref "MUX_1") (pin "16") (pinfunction "VCC_16") (pintype "power_in"))
      (node (ref "MUX_2") (pin "16") (pinfunction "VCC_16") (pintype "power_in"))
      (node (ref "PWR1") (pin "A") (pinfunction "A_A") (pintype "passive"))
      (node (ref "R1") (pin "2") (pinfunction "2_2") (pintype "passive"))
      (node (ref "R17") (pin "2") (pinfunction "2_2") (pintype "passive"))
      (node (ref "R18") (pin "2") (pinfunction "2_2") (pintype "passive"))
      (node (ref "R2") (pin "2") (pinfunction "2_2") (pintype "passive"))
      (node (ref "R3") (pin "2") (pinfunction "2_2") (pintype "passive"))
      (node (ref "R8") (pin "1") (pinfunction "1_1") (pintype "passive"))
      (node (ref "R9") (pin "2") (pinfunction "2_2") (pintype "passive"))
    )
    (net (code "69") (name "unconnected-(IC1-(AD0.3{slash}EINT3{slash}CAP0.0)P0.30-Pad15)") (class "Default")
      (node (ref "IC1") (pin "15") (pinfunction "(AD0.3/EINT3/CAP0.0)P0.30_15") (pintype "bidirectional"))
    )
    (net (code "70") (name "unconnected-(IC1-(AD0.5)P0.26-Pad10)") (class "Default")
      (node (ref "IC1") (pin "10") (pinfunction "(AD0.5)P0.26_10") (pintype "bidirectional"))
    )
    (net (code "71") (name "unconnected-(IC1-(MAT1.3{slash}SSEL1{slash}EINT3)P0.20-Pad55)") (class "Default")
      (node (ref "IC1") (pin "55") (pinfunction "(MAT1.3/SSEL1/EINT3)P0.20_55") (pintype "bidirectional"))
    )
    (net (code "72") (name "unconnected-(IC1-P0.23-Pad58)") (class "Default")
      (node (ref "IC1") (pin "58") (pinfunction "P0.23_58") (pintype "bidirectional"))
    )
    (net (code "73") (name "unconnected-(IC1-P1.16(TRACEPKT0)-Pad16)") (class "Default")
      (node (ref "IC1") (pin "16") (pinfunction "P1.16(TRACEPKT0)_16") (pintype "bidirectional"))
    )
    (net (code "74") (name "unconnected-(IC1-P1.17(TRACEPKT1)-Pad12)") (class "Default")
      (node (ref "IC1") (pin "12") (pinfunction "P1.17(TRACEPKT1)_12") (pintype "bidirectional"))
    )
    (net (code "75") (name "unconnected-(IC1-P1.18(TRACEPKT2)-Pad8)") (class "Default")
      (node (ref "IC1") (pin "8") (pinfunction "P1.18(TRACEPKT2)_8") (pintype "bidirectional"))
    )
    (net (code "76") (name "unconnected-(IC1-P1.19(TRACEPKT3)-Pad4)") (class "Default")
      (node (ref "IC1") (pin "4") (pinfunction "P1.19(TRACEPKT3)_4") (pintype "bidirectional"))
    )
    (net (code "77") (name "unconnected-(IC1-P1.20(TRACESYNC)-Pad48)") (class "Default")
      (node (ref "IC1") (pin "48") (pinfunction "P1.20(TRACESYNC)_48") (pintype "bidirectional"))
    )
    (net (code "78") (name "unconnected-(IC1-P1.21(PIPESTAT0)-Pad44)") (class "Default")
      (node (ref "IC1") (pin "44") (pinfunction "P1.21(PIPESTAT0)_44") (pintype "bidirectional"))
    )
    (net (code "79") (name "unconnected-(IC1-P1.22(PIPESTAT1)-Pad40)") (class "Default")
      (node (ref "IC1") (pin "40") (pinfunction "P1.22(PIPESTAT1)_40") (pintype "bidirectional"))
    )
    (net (code "80") (name "unconnected-(IC1-P1.23(PIPESTAT2)-Pad36)") (class "Default")
      (node (ref "IC1") (pin "36") (pinfunction "P1.23(PIPESTAT2)_36") (pintype "bidirectional"))
    )
    (net (code "81") (name "unconnected-(IC1-P1.24(TRACECLK)-Pad32)") (class "Default")
      (node (ref "IC1") (pin "32") (pinfunction "P1.24(TRACECLK)_32") (pintype "bidirectional"))
    )
    (net (code "82") (name "unconnected-(IC1-P1.25(EXTIN0)-Pad28)") (class "Default")
      (node (ref "IC1") (pin "28") (pinfunction "P1.25(EXTIN0)_28") (pintype "bidirectional"))
    )
    (net (code "83") (name "unconnected-(IC1-P1.26(RTCK)-Pad24)") (class "Default")
      (node (ref "IC1") (pin "24") (pinfunction "P1.26(RTCK)_24") (pintype "bidirectional"))
    )
    (net (code "84") (name "unconnected-(IC1-P1.27(TDO)-Pad64)") (class "Default")
      (node (ref "IC1") (pin "64") (pinfunction "P1.27(TDO)_64") (pintype "bidirectional"))
    )
    (net (code "85") (name "unconnected-(IC1-P1.28(TDI)-Pad60)") (class "Default")
      (node (ref "IC1") (pin "60") (pinfunction "P1.28(TDI)_60") (pintype "bidirectional"))
    )
    (net (code "86") (name "unconnected-(IC1-P1.29(TCK)-Pad56)") (class "Default")
      (node (ref "IC1") (pin "56") (pinfunction "P1.29(TCK)_56") (pintype "bidirectional"))
    )
    (net (code "87") (name "unconnected-(IC1-P1.30(TMS)-Pad52)") (class "Default")
      (node (ref "IC1") (pin "52") (pinfunction "P1.30(TMS)_52") (pintype "bidirectional"))
    )
    (net (code "88") (name "unconnected-(IC1-P1.31({slash}TRST)-Pad20)") (class "Default")
      (node (ref "IC1") (pin "20") (pinfunction "P1.31(/TRST)_20") (pintype "bidirectional"))
    )
    (net (code "89") (name "unconnected-(IC1-RTXC1-Pad3)") (class "Default")
      (node (ref "IC1") (pin "3") (pinfunction "RTXC1_3") (pintype "input"))
    )
    (net (code "90") (name "unconnected-(IC1-RTXC2-Pad5)") (class "Default")
      (node (ref "IC1") (pin "5") (pinfunction "RTXC2_5") (pintype "output"))
    )
  )
)
